# BatteryManagement.net
KiCad netlist of a schematic drawn in EAGLE
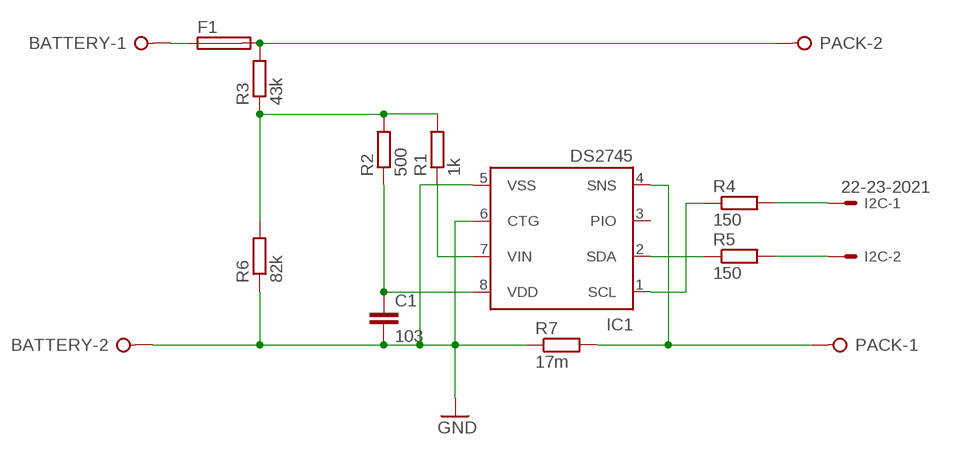
[diagram p0: schematic, sheet 1]

(export (version "E")
  (design (tool "Eeschema 10.0.6"))
  (components
    (comp (ref "BATTERY")
      (value "W237-02P")
      (footprint "eagle-import:W237-132")
      (libsource (lib "eagle-import") (part "W237-02P"))
    )
    (comp (ref "C1")
      (value "103")
      (footprint "eagle-import:C050-030X075")
      (libsource (lib "eagle-import") (part "C-EU050-030X075"))
    )
    (comp (ref "F1")
      (value "SH22,5")
      (footprint "eagle-import:SH22,5")
      (fields (field (name "MF") "SCHURTER") (field (name "MPN") "0031.8201"))
      (libsource (lib "eagle-import") (part "SH22,5"))
    )
    (comp (ref "I2C")
      (value "22-23-2021")
      (footprint "eagle-import:22-23-2021")
      (fields (field (name "MF") "MOLEX"))
      (libsource (lib "eagle-import") (part "22-23-2021"))
    )
    (comp (ref "IC1")
      (value "DS2745")
      (footprint "eagle-import:UMAX10")
      (libsource (lib "eagle-import") (part "DS2745"))
    )
    (comp (ref "PACK")
      (value "W237-02P")
      (footprint "eagle-import:W237-132")
      (libsource (lib "eagle-import") (part "W237-02P"))
    )
    (comp (ref "R1")
      (value "1k")
      (footprint "eagle-import:0207_10")
      (libsource (lib "eagle-import") (part "R-EU_0207/10"))
    )
    (comp (ref "R2")
      (value "500")
      (footprint "eagle-import:0207_10")
      (libsource (lib "eagle-import") (part "R-EU_0207/10"))
    )
    (comp (ref "R3")
      (value "43k")
      (footprint "eagle-import:0207_10")
      (libsource (lib "eagle-import") (part "R-EU_0207/10"))
    )
    (comp (ref "R4")
      (value "150")
      (footprint "eagle-import:0207_10")
      (libsource (lib "eagle-import") (part "R-EU_0207/10"))
    )
    (comp (ref "R5")
      (value "150")
      (footprint "eagle-import:0207_10")
      (libsource (lib "eagle-import") (part "R-EU_0207/10"))
    )
    (comp (ref "R6")
      (value "82k")
      (footprint "eagle-import:0207_10")
      (libsource (lib "eagle-import") (part "R-EU_0207/10"))
    )
    (comp (ref "R7")
      (value "17m")
      (footprint "eagle-import:M1206")
      (libsource (lib "eagle-import") (part "R-EU_M1206"))
    )
  )
  (nets
    (net (code "1") (name "GND") (class "Default")
      (node (ref "BATTERY") (pin "2") (pinfunction "KL_2") (pintype "passive"))
      (node (ref "C1") (pin "2") (pinfunction "2_2") (pintype "passive"))
      (node (ref "IC1") (pin "5") (pinfunction "VSS_5") (pintype "power_in"))
      (node (ref "IC1") (pin "6") (pinfunction "CTG_6") (pintype "power_in"))
      (node (ref "R6") (pin "1") (pinfunction "1_1") (pintype "passive"))
      (node (ref "R7") (pin "1") (pinfunction "1_1") (pintype "passive"))
    )
    (net (code "2") (name "Net-(BATTERYA-KL)") (class "Default")
      (node (ref "BATTERY") (pin "1") (pinfunction "KL_1") (pintype "passive"))
      (node (ref "F1") (pin "1") (pinfunction "1_1") (pintype "passive"))
    )
    (net (code "3") (name "Net-(I2CA-S)") (class "Default")
      (node (ref "I2C") (pin "1") (pinfunction "S_1") (pintype "passive"))
      (node (ref "R4") (pin "2") (pinfunction "2_2") (pintype "passive"))
    )
    (net (code "4") (name "Net-(I2CB-S)") (class "Default")
      (node (ref "I2C") (pin "2") (pinfunction "S_2") (pintype "passive"))
      (node (ref "R5") (pin "2") (pinfunction "2_2") (pintype "passive"))
    )
    (net (code "5") (name "Net-(IC1-SCL)") (class "Default")
      (node (ref "IC1") (pin "1") (pinfunction "SCL_1") (pintype "input"))
      (node (ref "R4") (pin "1") (pinfunction "1_1") (pintype "passive"))
    )
    (net (code "6") (name "Net-(IC1-SDA)") (class "Default")
      (node (ref "IC1") (pin "2") (pinfunction "SDA_2") (pintype "input"))
      (node (ref "R5") (pin "1") (pinfunction "1_1") (pintype "passive"))
    )
    (net (code "7") (name "Net-(IC1-SNS)") (class "Default")
      (node (ref "IC1") (pin "4") (pinfunction "SNS_4") (pintype "input"))
      (node (ref "PACK") (pin "1") (pinfunction "KL_1") (pintype "passive"))
      (node (ref "R7") (pin "2") (pinfunction "2_2") (pintype "passive"))
    )
    (net (code "8") (name "Net-(IC1-VDD)") (class "Default")
      (node (ref "C1") (pin "1") (pinfunction "1_1") (pintype "passive"))
      (node (ref "IC1") (pin "8") (pinfunction "VDD_8") (pintype "input"))
      (node (ref "R2") (pin "1") (pinfunction "1_1") (pintype "passive"))
    )
    (net (code "9") (name "Net-(IC1-VIN)") (class "Default")
      (node (ref "IC1") (pin "7") (pinfunction "VIN_7") (pintype "open_collector"))
      (node (ref "R1") (pin "1") (pinfunction "1_1") (pintype "passive"))
    )
    (net (code "10") (name "Net-(PACKB-KL)") (class "Default")
      (node (ref "F1") (pin "2") (pinfunction "2_2") (pintype "passive"))
      (node (ref "PACK") (pin "2") (pinfunction "KL_2") (pintype "passive"))
      (node (ref "R3") (pin "2") (pinfunction "2_2") (pintype "passive"))
    )
    (net (code "11") (name "Net-(R1-Pad2)") (class "Default")
      (node (ref "R1") (pin "2") (pinfunction "2_2") (pintype "passive"))
      (node (ref "R2") (pin "2") (pinfunction "2_2") (pintype "passive"))
      (node (ref "R3") (pin "1") (pinfunction "1_1") (pintype "passive"))
      (node (ref "R6") (pin "2") (pinfunction "2_2") (pintype "passive"))
    )
    (net (code "12") (name "unconnected-(IC1-PIO-Pad3)") (class "Default")
      (node (ref "IC1") (pin "3") (pinfunction "PIO_3") (pintype "input"))
    )
  )
)
